# MCU.net
KiCad netlist of a schematic drawn in Altium Designer
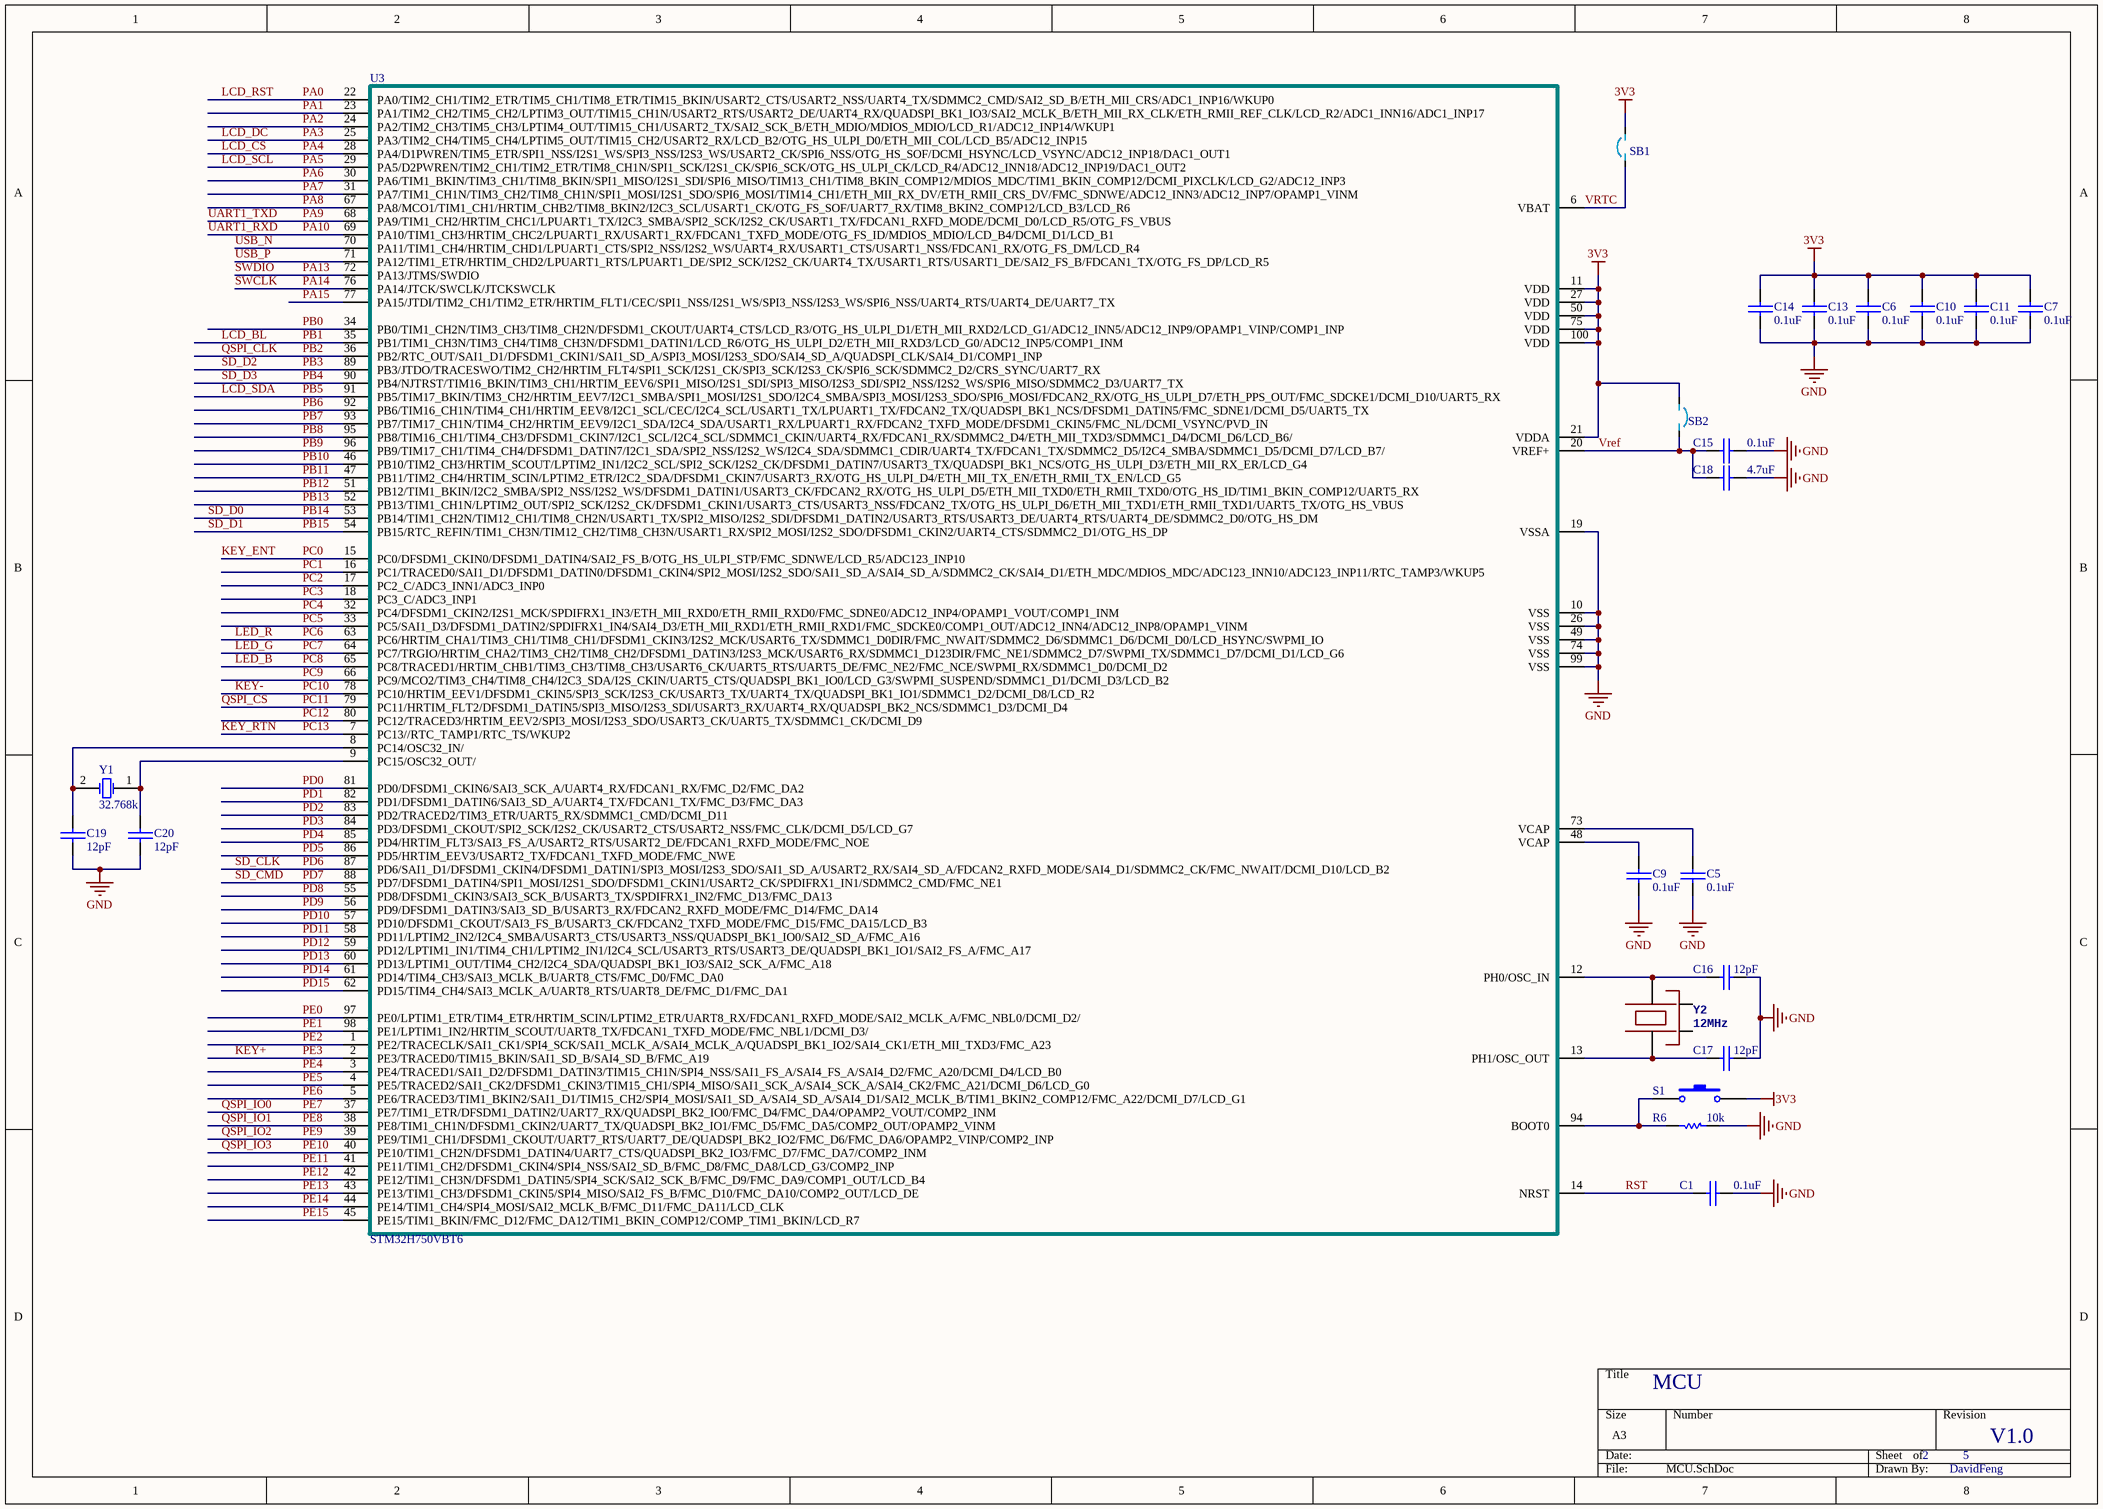
[diagram p0: MCU.SchDoc]

(export (version "E")
  (design (tool "Eeschema 10.0.6"))
  (components
    (comp (ref "C1")
      (value "0.1uF")
      (footprint "C0603")
      (description "Capacitor")
      (libsource (lib "Genius_Schlib") (part "CAP"))
    )
    (comp (ref "C5")
      (value "0.1uF")
      (footprint "C0603")
      (description "Capacitor")
      (libsource (lib "Genius_Schlib") (part "CAP"))
    )
    (comp (ref "C6")
      (value "0.1uF")
      (footprint "C0603")
      (description "Capacitor")
      (libsource (lib "Genius_Schlib") (part "CAP"))
    )
    (comp (ref "C7")
      (value "0.1uF")
      (footprint "C0603")
      (description "Capacitor")
      (libsource (lib "Genius_Schlib") (part "CAP"))
    )
    (comp (ref "C9")
      (value "0.1uF")
      (footprint "C0603")
      (description "Capacitor")
      (libsource (lib "Genius_Schlib") (part "CAP"))
    )
    (comp (ref "C10")
      (value "0.1uF")
      (footprint "C0603")
      (description "Capacitor")
      (libsource (lib "Genius_Schlib") (part "CAP"))
    )
    (comp (ref "C11")
      (value "0.1uF")
      (footprint "C0603")
      (description "Capacitor")
      (libsource (lib "Genius_Schlib") (part "CAP"))
    )
    (comp (ref "C13")
      (value "0.1uF")
      (footprint "C0603")
      (description "Capacitor")
      (libsource (lib "Genius_Schlib") (part "CAP"))
    )
    (comp (ref "C14")
      (value "0.1uF")
      (footprint "C0603")
      (description "Capacitor")
      (libsource (lib "Genius_Schlib") (part "CAP"))
    )
    (comp (ref "C15")
      (value "0.1uF")
      (footprint "C0603")
      (description "Capacitor")
      (libsource (lib "Genius_Schlib") (part "CAP"))
    )
    (comp (ref "C16")
      (value "12pF")
      (footprint "C0603")
      (description "Capacitor")
      (libsource (lib "Genius_Schlib") (part "CAP"))
    )
    (comp (ref "C17")
      (value "12pF")
      (footprint "C0603")
      (description "Capacitor")
      (libsource (lib "Genius_Schlib") (part "CAP"))
    )
    (comp (ref "C18")
      (value "4.7uF")
      (footprint "C0805")
      (description "Capacitor")
      (libsource (lib "Genius_Schlib") (part "CAP"))
    )
    (comp (ref "C19")
      (value "12pF")
      (footprint "C0603")
      (description "Capacitor")
      (libsource (lib "Genius_Schlib") (part "CAP"))
    )
    (comp (ref "C20")
      (value "12pF")
      (footprint "C0603")
      (description "Capacitor")
      (libsource (lib "Genius_Schlib") (part "CAP"))
    )
    (comp (ref "R6")
      (value "10k")
      (footprint "R0603")
      (description "Resistor")
      (fields (field (name "PUBLISHER") "Altium Limited"))
      (libsource (lib "Miscellaneous Devices") (part "Res1"))
    )
    (comp (ref "S1")
      (value "SW-PB")
      (footprint "SW_4X7_2P")
      (description "Switch")
      (fields (field (name "PUBLISHER") "Altium Limited"))
      (libsource (lib "Miscellaneous Devices") (part "SW-PB"))
    )
    (comp (ref "SB1") (value "Jumper") (footprint "SB0603") (libsource (lib "Genius_Schlib") (part "SB")))
    (comp (ref "SB2") (value "Jumper") (footprint "SB0603") (libsource (lib "Genius_Schlib") (part "SB")))
    (comp (ref "U3")
      (value "STM32H750VBT6")
      (footprint "TQFP-100")
      (description "STM32H750Vx")
      (libsource (lib "Genius_Schlib") (part "STM32H750Vx"))
    )
    (comp (ref "Y1")
      (value "32.768k")
      (footprint "FC-135")
      (description "Crystal Oscillator")
      (fields (field (name "PUBLISHER") "Altium Limited"))
      (libsource (lib "Miscellaneous Devices") (part "XTAL"))
    )
    (comp (ref "Y2")
      (value "12MHz")
      (footprint "SMD-3225")
      (description "CRYSTAL 24MHZ 8PF SMD")
      (libsource (lib "Genius_Schlib") (part "XTAL-4Pin"))
    )
  )
  (nets
    (net (code "1") (name "/KEY+") (class "Default")
      (node (ref "U3") (pin "2") (pinfunction "PE3/TRACED0/TIM15_BKIN/SAI1_SD_B/SAI4_SD_B/FMC_A19_2") (pintype "passive"))
    )
    (net (code "2") (name "/KEY-") (class "Default")
      (node (ref "U3") (pin "78") (pinfunction "PC10/HRTIM_EEV1/DFSDM1_CKIN5/SPI3_SCK/I2S3_CK/USART3_TX/UART4_TX/QUADSPI_BK1_IO1/SDMMC1_D2/DCMI_D8/LCD_R2_78") (pintype "passive"))
    )
    (net (code "3") (name "/KEY_ENT") (class "Default")
      (node (ref "U3") (pin "15") (pinfunction "PC0/DFSDM1_CKIN0/DFSDM1_DATIN4/SAI2_FS_B/OTG_HS_ULPI_STP/FMC_SDNWE/LCD_R5/ADC123_INP10_15") (pintype "passive"))
    )
    (net (code "4") (name "/KEY_RTN") (class "Default")
      (node (ref "U3") (pin "7") (pinfunction "PC13//RTC_TAMP1/RTC_TS/WKUP2_7") (pintype "passive"))
    )
    (net (code "5") (name "/LCD_BL") (class "Default")
      (node (ref "U3") (pin "35") (pinfunction "PB1/TIM1_CH3N/TIM3_CH4/TIM8_CH3N/DFSDM1_DATIN1/LCD_R6/OTG_HS_ULPI_D2/ETH_MII_RXD3/LCD_G0/ADC12_INP5/COMP1_INM_35") (pintype "passive"))
    )
    (net (code "6") (name "/LCD_CS") (class "Default")
      (node (ref "U3") (pin "28") (pinfunction "PA4/D1PWREN/TIM5_ETR/SPI1_NSS/I2S1_WS/SPI3_NSS/I2S3_WS/USART2_CK/SPI6_NSS/OTG_HS_SOF/DCMI_HSYNC/LCD_VSYNC/ADC12_INP18/DAC1_OUT1_28") (pintype "passive"))
    )
    (net (code "7") (name "/LCD_DC") (class "Default")
      (node (ref "U3") (pin "25") (pinfunction "PA3/TIM2_CH4/TIM5_CH4/LPTIM5_OUT/TIM15_CH2/USART2_RX/LCD_B2/OTG_HS_ULPI_D0/ETH_MII_COL/LCD_B5/ADC12_INP15_25") (pintype "passive"))
    )
    (net (code "8") (name "/LCD_RST") (class "Default")
      (node (ref "U3") (pin "22") (pinfunction "PA0/TIM2_CH1/TIM2_ETR/TIM5_CH1/TIM8_ETR/TIM15_BKIN/USART2_CTS/USART2_NSS/UART4_TX/SDMMC2_CMD/SAI2_SD_B/ETH_MII_CRS/ADC1_INP16/WKUP0_22") (pintype "passive"))
    )
    (net (code "9") (name "/LCD_SCL") (class "Default")
      (node (ref "U3") (pin "29") (pinfunction "PA5/D2PWREN/TIM2_CH1/TIM2_ETR/TIM8_CH1N/SPI1_SCK/I2S1_CK/SPI6_SCK/OTG_HS_ULPI_CK/LCD_R4/ADC12_INN18/ADC12_INP19/DAC1_OUT2_29") (pintype "passive"))
    )
    (net (code "10") (name "/LCD_SDA") (class "Default")
      (node (ref "U3") (pin "91") (pinfunction "PB5/TIM17_BKIN/TIM3_CH2/HRTIM_EEV7/I2C1_SMBA/SPI1_MOSI/I2S1_SDO/I2C4_SMBA/SPI3_MOSI/I2S3_SDO/SPI6_MOSI/FDCAN2_RX/OTG_HS_ULPI_D7/ETH_PPS_OUT/FMC_SDCKE1/DCMI_D10/UART5_RX_91") (pintype "passive"))
    )
    (net (code "11") (name "/LED_B") (class "Default")
      (node (ref "U3") (pin "65") (pinfunction "PC8/TRACED1/HRTIM_CHB1/TIM3_CH3/TIM8_CH3/USART6_CK/UART5_RTS/UART5_DE/FMC_NE2/FMC_NCE/SWPMI_RX/SDMMC1_D0/DCMI_D2_65") (pintype "passive"))
    )
    (net (code "12") (name "/LED_G") (class "Default")
      (node (ref "U3") (pin "64") (pinfunction "PC7/TRGIO/HRTIM_CHA2/TIM3_CH2/TIM8_CH2/DFSDM1_DATIN3/I2S3_MCK/USART6_RX/SDMMC1_D123DIR/FMC_NE1/SDMMC2_D7/SWPMI_TX/SDMMC1_D7/DCMI_D1/LCD_G6_64") (pintype "passive"))
    )
    (net (code "13") (name "/LED_R") (class "Default")
      (node (ref "U3") (pin "63") (pinfunction "PC6/HRTIM_CHA1/TIM3_CH1/TIM8_CH1/DFSDM1_CKIN3/I2S2_MCK/USART6_TX/SDMMC1_D0DIR/FMC_NWAIT/SDMMC2_D6/SDMMC1_D6/DCMI_D0/LCD_HSYNC/SWPMI_IO_63") (pintype "passive"))
    )
    (net (code "14") (name "/PA1") (class "Default")
      (node (ref "U3") (pin "23") (pinfunction "PA1/TIM2_CH2/TIM5_CH2/LPTIM3_OUT/TIM15_CH1N/USART2_RTS/USART2_DE/UART4_RX/QUADSPI_BK1_IO3/SAI2_MCLK_B/ETH_MII_RX_CLK/ETH_RMII_REF_CLK/LCD_R2/ADC1_INN16/ADC1_INP17_23") (pintype "passive"))
    )
    (net (code "15") (name "/PA2") (class "Default")
      (node (ref "U3") (pin "24") (pinfunction "PA2/TIM2_CH3/TIM5_CH3/LPTIM4_OUT/TIM15_CH1/USART2_TX/SAI2_SCK_B/ETH_MDIO/MDIOS_MDIO/LCD_R1/ADC12_INP14/WKUP1_24") (pintype "passive"))
    )
    (net (code "16") (name "/PA6") (class "Default")
      (node (ref "U3") (pin "30") (pinfunction "PA6/TIM1_BKIN/TIM3_CH1/TIM8_BKIN/SPI1_MISO/I2S1_SDI/SPI6_MISO/TIM13_CH1/TIM8_BKIN_COMP12/MDIOS_MDC/TIM1_BKIN_COMP12/DCMI_PIXCLK/LCD_G2/ADC12_INP3_30") (pintype "passive"))
    )
    (net (code "17") (name "/PA7") (class "Default")
      (node (ref "U3") (pin "31") (pinfunction "PA7/TIM1_CH1N/TIM3_CH2/TIM8_CH1N/SPI1_MOSI/I2S1_SDO/SPI6_MOSI/TIM14_CH1/ETH_MII_RX_DV/ETH_RMII_CRS_DV/FMC_SDNWE/ADC12_INN3/ADC12_INP7/OPAMP1_VINM_31") (pintype "passive"))
    )
    (net (code "18") (name "/PA8") (class "Default")
      (node (ref "U3") (pin "67") (pinfunction "PA8/MCO1/TIM1_CH1/HRTIM_CHB2/TIM8_BKIN2/I2C3_SCL/USART1_CK/OTG_FS_SOF/UART7_RX/TIM8_BKIN2_COMP12/LCD_B3/LCD_R6_67") (pintype "passive"))
    )
    (net (code "19") (name "/PA9") (class "Default")
      (node (ref "U3") (pin "68") (pinfunction "PA9/TIM1_CH2/HRTIM_CHC1/LPUART1_TX/I2C3_SMBA/SPI2_SCK/I2S2_CK/USART1_TX/FDCAN1_RXFD_MODE/DCMI_D0/LCD_R5/OTG_FS_VBUS_68") (pintype "passive"))
    )
    (net (code "20") (name "/PA10") (class "Default")
      (node (ref "U3") (pin "69") (pinfunction "PA10/TIM1_CH3/HRTIM_CHC2/LPUART1_RX/USART1_RX/FDCAN1_TXFD_MODE/OTG_FS_ID/MDIOS_MDIO/LCD_B4/DCMI_D1/LCD_B1_69") (pintype "passive"))
    )
    (net (code "21") (name "/PA13") (class "Default")
      (node (ref "U3") (pin "72") (pinfunction "PA13/JTMS/SWDIO_72") (pintype "passive"))
    )
    (net (code "22") (name "/PA14") (class "Default")
      (node (ref "U3") (pin "76") (pinfunction "PA14/JTCK/SWCLK/JTCKSWCLK_76") (pintype "passive"))
    )
    (net (code "23") (name "/PA15") (class "Default")
      (node (ref "U3") (pin "77") (pinfunction "PA15/JTDI/TIM2_CH1/TIM2_ETR/HRTIM_FLT1/CEC/SPI1_NSS/I2S1_WS/SPI3_NSS/I2S3_WS/SPI6_NSS/UART4_RTS/UART4_DE/UART7_TX_77") (pintype "passive"))
    )
    (net (code "24") (name "/PB0") (class "Default")
      (node (ref "U3") (pin "34") (pinfunction "PB0/TIM1_CH2N/TIM3_CH3/TIM8_CH2N/DFSDM1_CKOUT/UART4_CTS/LCD_R3/OTG_HS_ULPI_D1/ETH_MII_RXD2/LCD_G1/ADC12_INN5/ADC12_INP9/OPAMP1_VINP/COMP1_INP_34") (pintype "passive"))
    )
    (net (code "25") (name "/PB2") (class "Default")
      (node (ref "U3") (pin "36") (pinfunction "PB2/RTC_OUT/SAI1_D1/DFSDM1_CKIN1/SAI1_SD_A/SPI3_MOSI/I2S3_SDO/SAI4_SD_A/QUADSPI_CLK/SAI4_D1/COMP1_INP_36") (pintype "passive"))
    )
    (net (code "26") (name "/PB3") (class "Default")
      (node (ref "U3") (pin "89") (pinfunction "PB3/JTDO/TRACESWO/TIM2_CH2/HRTIM_FLT4/SPI1_SCK/I2S1_CK/SPI3_SCK/I2S3_CK/SPI6_SCK/SDMMC2_D2/CRS_SYNC/UART7_RX_89") (pintype "passive"))
    )
    (net (code "27") (name "/PB4") (class "Default")
      (node (ref "U3") (pin "90") (pinfunction "PB4/NJTRST/TIM16_BKIN/TIM3_CH1/HRTIM_EEV6/SPI1_MISO/I2S1_SDI/SPI3_MISO/I2S3_SDI/SPI2_NSS/I2S2_WS/SPI6_MISO/SDMMC2_D3/UART7_TX_90") (pintype "passive"))
    )
    (net (code "28") (name "/PB6") (class "Default")
      (node (ref "U3") (pin "92") (pinfunction "PB6/TIM16_CH1N/TIM4_CH1/HRTIM_EEV8/I2C1_SCL/CEC/I2C4_SCL/USART1_TX/LPUART1_TX/FDCAN2_TX/QUADSPI_BK1_NCS/DFSDM1_DATIN5/FMC_SDNE1/DCMI_D5/UART5_TX_92") (pintype "passive"))
    )
    (net (code "29") (name "/PB7") (class "Default")
      (node (ref "U3") (pin "93") (pinfunction "PB7/TIM17_CH1N/TIM4_CH2/HRTIM_EEV9/I2C1_SDA/I2C4_SDA/USART1_RX/LPUART1_RX/FDCAN2_TXFD_MODE/DFSDM1_CKIN5/FMC_NL/DCMI_VSYNC/PVD_IN_93") (pintype "passive"))
    )
    (net (code "30") (name "/PB8") (class "Default")
      (node (ref "U3") (pin "95") (pinfunction "PB8/TIM16_CH1/TIM4_CH3/DFSDM1_CKIN7/I2C1_SCL/I2C4_SCL/SDMMC1_CKIN/UART4_RX/FDCAN1_RX/SDMMC2_D4/ETH_MII_TXD3/SDMMC1_D4/DCMI_D6/LCD_B6/_95") (pintype "passive"))
    )
    (net (code "31") (name "/PB9") (class "Default")
      (node (ref "U3") (pin "96") (pinfunction "PB9/TIM17_CH1/TIM4_CH4/DFSDM1_DATIN7/I2C1_SDA/SPI2_NSS/I2S2_WS/I2C4_SDA/SDMMC1_CDIR/UART4_TX/FDCAN1_TX/SDMMC2_D5/I2C4_SMBA/SDMMC1_D5/DCMI_D7/LCD_B7/_96") (pintype "passive"))
    )
    (net (code "32") (name "/PB10") (class "Default")
      (node (ref "U3") (pin "46") (pinfunction "PB10/TIM2_CH3/HRTIM_SCOUT/LPTIM2_IN1/I2C2_SCL/SPI2_SCK/I2S2_CK/DFSDM1_DATIN7/USART3_TX/QUADSPI_BK1_NCS/OTG_HS_ULPI_D3/ETH_MII_RX_ER/LCD_G4_46") (pintype "passive"))
    )
    (net (code "33") (name "/PB11") (class "Default")
      (node (ref "U3") (pin "47") (pinfunction "PB11/TIM2_CH4/HRTIM_SCIN/LPTIM2_ETR/I2C2_SDA/DFSDM1_CKIN7/USART3_RX/OTG_HS_ULPI_D4/ETH_MII_TX_EN/ETH_RMII_TX_EN/LCD_G5_47") (pintype "passive"))
    )
    (net (code "34") (name "/PB12") (class "Default")
      (node (ref "U3") (pin "51") (pinfunction "PB12/TIM1_BKIN/I2C2_SMBA/SPI2_NSS/I2S2_WS/DFSDM1_DATIN1/USART3_CK/FDCAN2_RX/OTG_HS_ULPI_D5/ETH_MII_TXD0/ETH_RMII_TXD0/OTG_HS_ID/TIM1_BKIN_COMP12/UART5_RX_51") (pintype "passive"))
    )
    (net (code "35") (name "/PB13") (class "Default")
      (node (ref "U3") (pin "52") (pinfunction "PB13/TIM1_CH1N/LPTIM2_OUT/SPI2_SCK/I2S2_CK/DFSDM1_CKIN1/USART3_CTS/USART3_NSS/FDCAN2_TX/OTG_HS_ULPI_D6/ETH_MII_TXD1/ETH_RMII_TXD1/UART5_TX/OTG_HS_VBUS_52") (pintype "passive"))
    )
    (net (code "36") (name "/PB14") (class "Default")
      (node (ref "U3") (pin "53") (pinfunction "PB14/TIM1_CH2N/TIM12_CH1/TIM8_CH2N/USART1_TX/SPI2_MISO/I2S2_SDI/DFSDM1_DATIN2/USART3_RTS/USART3_DE/UART4_RTS/UART4_DE/SDMMC2_D0/OTG_HS_DM_53") (pintype "passive"))
    )
    (net (code "37") (name "/PB15") (class "Default")
      (node (ref "U3") (pin "54") (pinfunction "PB15/RTC_REFIN/TIM1_CH3N/TIM12_CH2/TIM8_CH3N/USART1_RX/SPI2_MOSI/I2S2_SDO/DFSDM1_CKIN2/UART4_CTS/SDMMC2_D1/OTG_HS_DP_54") (pintype "passive"))
    )
    (net (code "38") (name "/PC1") (class "Default")
      (node (ref "U3") (pin "16") (pinfunction "PC1/TRACED0/SAI1_D1/DFSDM1_DATIN0/DFSDM1_CKIN4/SPI2_MOSI/I2S2_SDO/SAI1_SD_A/SAI4_SD_A/SDMMC2_CK/SAI4_D1/ETH_MDC/MDIOS_MDC/ADC123_INN10/ADC123_INP11/RTC_TAMP3/WKUP5_16") (pintype "passive"))
    )
    (net (code "39") (name "/PC2") (class "Default")
      (node (ref "U3") (pin "17") (pinfunction "PC2_C/ADC3_INN1/ADC3_INP0_17") (pintype "passive"))
    )
    (net (code "40") (name "/PC3") (class "Default")
      (node (ref "U3") (pin "18") (pinfunction "PC3_C/ADC3_INP1_18") (pintype "passive"))
    )
    (net (code "41") (name "/PC4") (class "Default")
      (node (ref "U3") (pin "32") (pinfunction "PC4/DFSDM1_CKIN2/I2S1_MCK/SPDIFRX1_IN3/ETH_MII_RXD0/ETH_RMII_RXD0/FMC_SDNE0/ADC12_INP4/OPAMP1_VOUT/COMP1_INM_32") (pintype "passive"))
    )
    (net (code "42") (name "/PC5") (class "Default")
      (node (ref "U3") (pin "33") (pinfunction "PC5/SAI1_D3/DFSDM1_DATIN2/SPDIFRX1_IN4/SAI4_D3/ETH_MII_RXD1/ETH_RMII_RXD1/FMC_SDCKE0/COMP1_OUT/ADC12_INN4/ADC12_INP8/OPAMP1_VINM_33") (pintype "passive"))
    )
    (net (code "43") (name "/PC9") (class "Default")
      (node (ref "U3") (pin "66") (pinfunction "PC9/MCO2/TIM3_CH4/TIM8_CH4/I2C3_SDA/I2S_CKIN/UART5_CTS/QUADSPI_BK1_IO0/LCD_G3/SWPMI_SUSPEND/SDMMC1_D1/DCMI_D3/LCD_B2_66") (pintype "passive"))
    )
    (net (code "44") (name "/PC11") (class "Default")
      (node (ref "U3") (pin "79") (pinfunction "PC11/HRTIM_FLT2/DFSDM1_DATIN5/SPI3_MISO/I2S3_SDI/USART3_RX/UART4_RX/QUADSPI_BK2_NCS/SDMMC1_D3/DCMI_D4_79") (pintype "passive"))
    )
    (net (code "45") (name "/PC12") (class "Default")
      (node (ref "U3") (pin "80") (pinfunction "PC12/TRACED3/HRTIM_EEV2/SPI3_MOSI/I2S3_SDO/USART3_CK/UART5_TX/SDMMC1_CK/DCMI_D9_80") (pintype "passive"))
    )
    (net (code "46") (name "/PD0") (class "Default")
      (node (ref "U3") (pin "81") (pinfunction "PD0/DFSDM1_CKIN6/SAI3_SCK_A/UART4_RX/FDCAN1_RX/FMC_D2/FMC_DA2_81") (pintype "passive"))
    )
    (net (code "47") (name "/PD1") (class "Default")
      (node (ref "U3") (pin "82") (pinfunction "PD1/DFSDM1_DATIN6/SAI3_SD_A/UART4_TX/FDCAN1_TX/FMC_D3/FMC_DA3_82") (pintype "passive"))
    )
    (net (code "48") (name "/PD2") (class "Default")
      (node (ref "U3") (pin "83") (pinfunction "PD2/TRACED2/TIM3_ETR/UART5_RX/SDMMC1_CMD/DCMI_D11_83") (pintype "passive"))
    )
    (net (code "49") (name "/PD3") (class "Default")
      (node (ref "U3") (pin "84") (pinfunction "PD3/DFSDM1_CKOUT/SPI2_SCK/I2S2_CK/USART2_CTS/USART2_NSS/FMC_CLK/DCMI_D5/LCD_G7_84") (pintype "passive"))
    )
    (net (code "50") (name "/PD4") (class "Default")
      (node (ref "U3") (pin "85") (pinfunction "PD4/HRTIM_FLT3/SAI3_FS_A/USART2_RTS/USART2_DE/FDCAN1_RXFD_MODE/FMC_NOE_85") (pintype "passive"))
    )
    (net (code "51") (name "/PD5") (class "Default")
      (node (ref "U3") (pin "86") (pinfunction "PD5/HRTIM_EEV3/USART2_TX/FDCAN1_TXFD_MODE/FMC_NWE_86") (pintype "passive"))
    )
    (net (code "52") (name "/PD6") (class "Default")
      (node (ref "U3") (pin "87") (pinfunction "PD6/SAI1_D1/DFSDM1_CKIN4/DFSDM1_DATIN1/SPI3_MOSI/I2S3_SDO/SAI1_SD_A/USART2_RX/SAI4_SD_A/FDCAN2_RXFD_MODE/SAI4_D1/SDMMC2_CK/FMC_NWAIT/DCMI_D10/LCD_B2_87") (pintype "passive"))
    )
    (net (code "53") (name "/PD7") (class "Default")
      (node (ref "U3") (pin "88") (pinfunction "PD7/DFSDM1_DATIN4/SPI1_MOSI/I2S1_SDO/DFSDM1_CKIN1/USART2_CK/SPDIFRX1_IN1/SDMMC2_CMD/FMC_NE1_88") (pintype "passive"))
    )
    (net (code "54") (name "/PD8") (class "Default")
      (node (ref "U3") (pin "55") (pinfunction "PD8/DFSDM1_CKIN3/SAI3_SCK_B/USART3_TX/SPDIFRX1_IN2/FMC_D13/FMC_DA13_55") (pintype "passive"))
    )
    (net (code "55") (name "/PD9") (class "Default")
      (node (ref "U3") (pin "56") (pinfunction "PD9/DFSDM1_DATIN3/SAI3_SD_B/USART3_RX/FDCAN2_RXFD_MODE/FMC_D14/FMC_DA14_56") (pintype "passive"))
    )
    (net (code "56") (name "/PD10") (class "Default")
      (node (ref "U3") (pin "57") (pinfunction "PD10/DFSDM1_CKOUT/SAI3_FS_B/USART3_CK/FDCAN2_TXFD_MODE/FMC_D15/FMC_DA15/LCD_B3_57") (pintype "passive"))
    )
    (net (code "57") (name "/PD11") (class "Default")
      (node (ref "U3") (pin "58") (pinfunction "PD11/LPTIM2_IN2/I2C4_SMBA/USART3_CTS/USART3_NSS/QUADSPI_BK1_IO0/SAI2_SD_A/FMC_A16_58") (pintype "passive"))
    )
    (net (code "58") (name "/PD12") (class "Default")
      (node (ref "U3") (pin "59") (pinfunction "PD12/LPTIM1_IN1/TIM4_CH1/LPTIM2_IN1/I2C4_SCL/USART3_RTS/USART3_DE/QUADSPI_BK1_IO1/SAI2_FS_A/FMC_A17_59") (pintype "passive"))
    )
    (net (code "59") (name "/PD13") (class "Default")
      (node (ref "U3") (pin "60") (pinfunction "PD13/LPTIM1_OUT/TIM4_CH2/I2C4_SDA/QUADSPI_BK1_IO3/SAI2_SCK_A/FMC_A18_60") (pintype "passive"))
    )
    (net (code "60") (name "/PD14") (class "Default")
      (node (ref "U3") (pin "61") (pinfunction "PD14/TIM4_CH3/SAI3_MCLK_B/UART8_CTS/FMC_D0/FMC_DA0_61") (pintype "passive"))
    )
    (net (code "61") (name "/PD15") (class "Default")
      (node (ref "U3") (pin "62") (pinfunction "PD15/TIM4_CH4/SAI3_MCLK_A/UART8_RTS/UART8_DE/FMC_D1/FMC_DA1_62") (pintype "passive"))
    )
    (net (code "62") (name "/PE0") (class "Default")
      (node (ref "U3") (pin "97") (pinfunction "PE0/LPTIM1_ETR/TIM4_ETR/HRTIM_SCIN/LPTIM2_ETR/UART8_RX/FDCAN1_RXFD_MODE/SAI2_MCLK_A/FMC_NBL0/DCMI_D2/_97") (pintype "passive"))
    )
    (net (code "63") (name "/PE1") (class "Default")
      (node (ref "U3") (pin "98") (pinfunction "PE1/LPTIM1_IN2/HRTIM_SCOUT/UART8_TX/FDCAN1_TXFD_MODE/FMC_NBL1/DCMI_D3/_98") (pintype "passive"))
    )
    (net (code "64") (name "/PE2") (class "Default")
      (node (ref "U3") (pin "1") (pinfunction "PE2/TRACECLK/SAI1_CK1/SPI4_SCK/SAI1_MCLK_A/SAI4_MCLK_A/QUADSPI_BK1_IO2/SAI4_CK1/ETH_MII_TXD3/FMC_A23_1") (pintype "passive"))
    )
    (net (code "65") (name "/PE4") (class "Default")
      (node (ref "U3") (pin "3") (pinfunction "PE4/TRACED1/SAI1_D2/DFSDM1_DATIN3/TIM15_CH1N/SPI4_NSS/SAI1_FS_A/SAI4_FS_A/SAI4_D2/FMC_A20/DCMI_D4/LCD_B0_3") (pintype "passive"))
    )
    (net (code "66") (name "/PE5") (class "Default")
      (node (ref "U3") (pin "4") (pinfunction "PE5/TRACED2/SAI1_CK2/DFSDM1_CKIN3/TIM15_CH1/SPI4_MISO/SAI1_SCK_A/SAI4_SCK_A/SAI4_CK2/FMC_A21/DCMI_D6/LCD_G0_4") (pintype "passive"))
    )
    (net (code "67") (name "/PE6") (class "Default")
      (node (ref "U3") (pin "5") (pinfunction "PE6/TRACED3/TIM1_BKIN2/SAI1_D1/TIM15_CH2/SPI4_MOSI/SAI1_SD_A/SAI4_SD_A/SAI4_D1/SAI2_MCLK_B/TIM1_BKIN2_COMP12/FMC_A22/DCMI_D7/LCD_G1_5") (pintype "passive"))
    )
    (net (code "68") (name "/PE7") (class "Default")
      (node (ref "U3") (pin "37") (pinfunction "PE7/TIM1_ETR/DFSDM1_DATIN2/UART7_RX/QUADSPI_BK2_IO0/FMC_D4/FMC_DA4/OPAMP2_VOUT/COMP2_INM_37") (pintype "passive"))
    )
    (net (code "69") (name "/PE8") (class "Default")
      (node (ref "U3") (pin "38") (pinfunction "PE8/TIM1_CH1N/DFSDM1_CKIN2/UART7_TX/QUADSPI_BK2_IO1/FMC_D5/FMC_DA5/COMP2_OUT/OPAMP2_VINM_38") (pintype "passive"))
    )
    (net (code "70") (name "/PE9") (class "Default")
      (node (ref "U3") (pin "39") (pinfunction "PE9/TIM1_CH1/DFSDM1_CKOUT/UART7_RTS/UART7_DE/QUADSPI_BK2_IO2/FMC_D6/FMC_DA6/OPAMP2_VINP/COMP2_INP_39") (pintype "passive"))
    )
    (net (code "71") (name "/PE10") (class "Default")
      (node (ref "U3") (pin "40") (pinfunction "PE10/TIM1_CH2N/DFSDM1_DATIN4/UART7_CTS/QUADSPI_BK2_IO3/FMC_D7/FMC_DA7/COMP2_INM_40") (pintype "passive"))
    )
    (net (code "72") (name "/PE11") (class "Default")
      (node (ref "U3") (pin "41") (pinfunction "PE11/TIM1_CH2/DFSDM1_CKIN4/SPI4_NSS/SAI2_SD_B/FMC_D8/FMC_DA8/LCD_G3/COMP2_INP_41") (pintype "passive"))
    )
    (net (code "73") (name "/PE12") (class "Default")
      (node (ref "U3") (pin "42") (pinfunction "PE12/TIM1_CH3N/DFSDM1_DATIN5/SPI4_SCK/SAI2_SCK_B/FMC_D9/FMC_DA9/COMP1_OUT/LCD_B4_42") (pintype "passive"))
    )
    (net (code "74") (name "/PE13") (class "Default")
      (node (ref "U3") (pin "43") (pinfunction "PE13/TIM1_CH3/DFSDM1_CKIN5/SPI4_MISO/SAI2_FS_B/FMC_D10/FMC_DA10/COMP2_OUT/LCD_DE_43") (pintype "passive"))
    )
    (net (code "75") (name "/PE14") (class "Default")
      (node (ref "U3") (pin "44") (pinfunction "PE14/TIM1_CH4/SPI4_MOSI/SAI2_MCLK_B/FMC_D11/FMC_DA11/LCD_CLK_44") (pintype "passive"))
    )
    (net (code "76") (name "/PE15") (class "Default")
      (node (ref "U3") (pin "45") (pinfunction "PE15/TIM1_BKIN/FMC_D12/FMC_DA12/TIM1_BKIN_COMP12/COMP_TIM1_BKIN/LCD_R7_45") (pintype "passive"))
    )
    (net (code "77") (name "/RST") (class "Default")
      (node (ref "C1") (pin "1") (pinfunction "1_1") (pintype "passive"))
      (node (ref "U3") (pin "14") (pinfunction "NRST_14") (pintype "passive"))
    )
    (net (code "78") (name "/USB_N") (class "Default")
      (node (ref "U3") (pin "70") (pinfunction "PA11/TIM1_CH4/HRTIM_CHD1/LPUART1_CTS/SPI2_NSS/I2S2_WS/UART4_RX/USART1_CTS/USART1_NSS/FDCAN1_RX/OTG_FS_DM/LCD_R4_70") (pintype "passive"))
    )
    (net (code "79") (name "/USB_P") (class "Default")
      (node (ref "U3") (pin "71") (pinfunction "PA12/TIM1_ETR/HRTIM_CHD2/LPUART1_RTS/LPUART1_DE/SPI2_SCK/I2S2_CK/UART4_TX/USART1_RTS/USART1_DE/SAI2_FS_B/FDCAN1_TX/OTG_FS_DP/LCD_R5_71") (pintype "passive"))
    )
    (net (code "80") (name "/VRTC") (class "Default")
      (node (ref "SB1") (pin "2") (pinfunction "2_2") (pintype "passive"))
      (node (ref "U3") (pin "6") (pinfunction "VBAT_6") (pintype "passive"))
    )
    (net (code "81") (name "/Vref") (class "Default")
      (node (ref "C15") (pin "1") (pinfunction "1_1") (pintype "passive"))
      (node (ref "C18") (pin "1") (pinfunction "1_1") (pintype "passive"))
      (node (ref "SB2") (pin "1") (pinfunction "1_1") (pintype "passive"))
      (node (ref "U3") (pin "20") (pinfunction "VREF+_20") (pintype "passive"))
    )
    (net (code "82") (name "3V3") (class "Default")
      (node (ref "C10") (pin "2") (pinfunction "2_2") (pintype "passive"))
      (node (ref "C11") (pin "1") (pinfunction "1_1") (pintype "passive"))
      (node (ref "C13") (pin "2") (pinfunction "2_2") (pintype "passive"))
      (node (ref "C14") (pin "2") (pinfunction "2_2") (pintype "passive"))
      (node (ref "C6") (pin "1") (pinfunction "1_1") (pintype "passive"))
      (node (ref "C7") (pin "1") (pinfunction "1_1") (pintype "passive"))
      (node (ref "S1") (pin "2") (pinfunction "2_2") (pintype "passive"))
      (node (ref "SB1") (pin "1") (pinfunction "1_1") (pintype "passive"))
      (node (ref "SB2") (pin "2") (pinfunction "2_2") (pintype "passive"))
      (node (ref "U3") (pin "100") (pinfunction "VDD_100") (pintype "passive"))
      (node (ref "U3") (pin "11") (pinfunction "VDD_11") (pintype "passive"))
      (node (ref "U3") (pin "21") (pinfunction "VDDA_21") (pintype "passive"))
      (node (ref "U3") (pin "27") (pinfunction "VDD_27") (pintype "passive"))
      (node (ref "U3") (pin "50") (pinfunction "VDD_50") (pintype "passive"))
      (node (ref "U3") (pin "75") (pinfunction "VDD_75") (pintype "passive"))
    )
    (net (code "83") (name "GND") (class "Default")
      (node (ref "C1") (pin "2") (pinfunction "2_2") (pintype "passive"))
      (node (ref "C10") (pin "1") (pinfunction "1_1") (pintype "passive"))
      (node (ref "C11") (pin "2") (pinfunction "2_2") (pintype "passive"))
      (node (ref "C13") (pin "1") (pinfunction "1_1") (pintype "passive"))
      (node (ref "C14") (pin "1") (pinfunction "1_1") (pintype "passive"))
      (node (ref "C15") (pin "2") (pinfunction "2_2") (pintype "passive"))
      (node (ref "C16") (pin "1") (pinfunction "1_1") (pintype "passive"))
      (node (ref "C17") (pin "1") (pinfunction "1_1") (pintype "passive"))
      (node (ref "C18") (pin "2") (pinfunction "2_2") (pintype "passive"))
      (node (ref "C19") (pin "1") (pinfunction "1_1") (pintype "passive"))
      (node (ref "C20") (pin "1") (pinfunction "1_1") (pintype "passive"))
      (node (ref "C5") (pin "2") (pinfunction "2_2") (pintype "passive"))
      (node (ref "C6") (pin "2") (pinfunction "2_2") (pintype "passive"))
      (node (ref "C7") (pin "2") (pinfunction "2_2") (pintype "passive"))
      (node (ref "C9") (pin "2") (pinfunction "2_2") (pintype "passive"))
      (node (ref "R6") (pin "2") (pinfunction "2_2") (pintype "passive"))
      (node (ref "U3") (pin "10") (pinfunction "VSS_10") (pintype "passive"))
      (node (ref "U3") (pin "19") (pinfunction "VSSA_19") (pintype "passive"))
      (node (ref "U3") (pin "26") (pinfunction "VSS_26") (pintype "passive"))
      (node (ref "U3") (pin "49") (pinfunction "VSS_49") (pintype "passive"))
      (node (ref "U3") (pin "74") (pinfunction "VSS_74") (pintype "passive"))
      (node (ref "U3") (pin "99") (pinfunction "VSS_99") (pintype "passive"))
    )
    (net (code "84") (name "Net-(C5-Pad1)") (class "Default")
      (node (ref "C5") (pin "1") (pinfunction "1_1") (pintype "passive"))
      (node (ref "U3") (pin "73") (pinfunction "VCAP_73") (pintype "passive"))
    )
    (net (code "85") (name "Net-(C9-Pad1)") (class "Default")
      (node (ref "C9") (pin "1") (pinfunction "1_1") (pintype "passive"))
      (node (ref "U3") (pin "48") (pinfunction "VCAP_48") (pintype "passive"))
    )
    (net (code "86") (name "Net-(U3-BOOT0)") (class "Default")
      (node (ref "R6") (pin "1") (pinfunction "1_1") (pintype "passive"))
      (node (ref "S1") (pin "1") (pinfunction "1_1") (pintype "passive"))
      (node (ref "U3") (pin "94") (pinfunction "BOOT0_94") (pintype "passive"))
    )
    (net (code "87") (name "Net-(U3-PC14{slash}OSC32_IN{slash})") (class "Default")
      (node (ref "C19") (pin "2") (pinfunction "2_2") (pintype "passive"))
      (node (ref "U3") (pin "8") (pinfunction "PC14/OSC32_IN/_8") (pintype "passive"))
      (node (ref "Y1") (pin "2") (pinfunction "OSC2_2") (pintype "passive"))
    )
    (net (code "88") (name "Net-(U3-PC15{slash}OSC32_OUT{slash})") (class "Default")
      (node (ref "C20") (pin "2") (pinfunction "2_2") (pintype "passive"))
      (node (ref "U3") (pin "9") (pinfunction "PC15/OSC32_OUT/_9") (pintype "passive"))
      (node (ref "Y1") (pin "1") (pinfunction "OSC1_1") (pintype "passive"))
    )
    (net (code "89") (name "Net-(U3-PH0{slash}OSC_IN)") (class "Default")
      (node (ref "C16") (pin "2") (pinfunction "2_2") (pintype "passive"))
      (node (ref "U3") (pin "12") (pinfunction "PH0/OSC_IN_12") (pintype "passive"))
      (node (ref "Y2") (pin "3") (pinfunction "3_3") (pintype "passive"))
    )
    (net (code "90") (name "Net-(U3-PH1{slash}OSC_OUT)") (class "Default")
      (node (ref "C17") (pin "2") (pinfunction "2_2") (pintype "passive"))
      (node (ref "U3") (pin "13") (pinfunction "PH1/OSC_OUT_13") (pintype "passive"))
      (node (ref "Y2") (pin "1") (pinfunction "1_1") (pintype "passive"))
    )
    (net (code "91") (name "unconnected-(Y2-NC_2-Pad2)") (class "Default")
      (node (ref "Y2") (pin "2") (pinfunction "NC_2_2") (pintype "open_emitter"))
    )
    (net (code "92") (name "unconnected-(Y2-NC_4-Pad4)") (class "Default")
      (node (ref "Y2") (pin "4") (pinfunction "NC_4_4") (pintype "open_emitter"))
    )
  )
)
